# PR9024.net
KiCad netlist of a schematic drawn in EAGLE
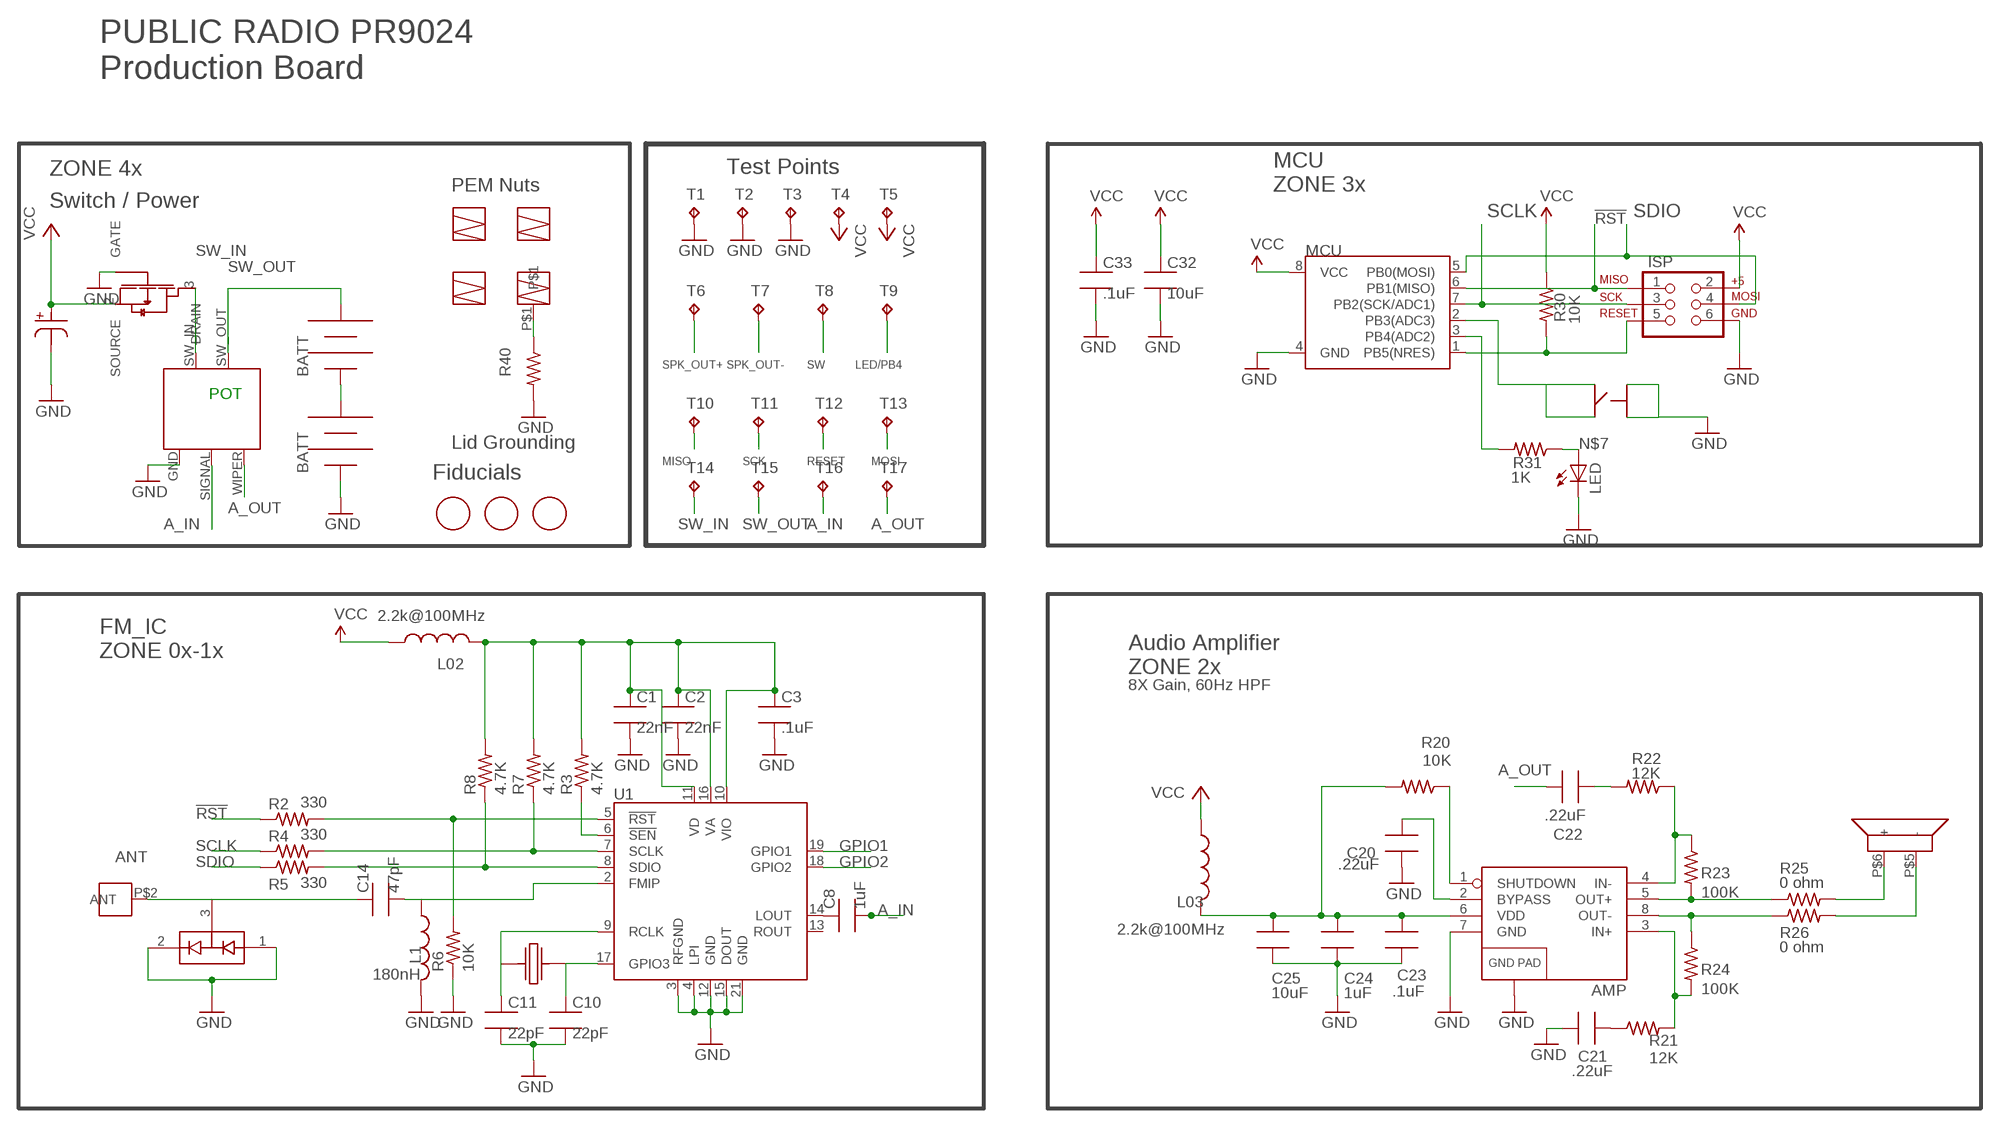
[diagram p0: schematic, sheet 1]

(export (version "E")
  (design (tool "Eeschema 10.0.6"))
  (components
    (comp (ref "AMP")
      (value "TPA6203A1")
      (footprint "eagle-import:8-MSOP")
      (libsource (lib "eagle-import") (part "TPA6203A1"))
    )
    (comp (ref "ANT_MOUNT")
      (value "DNP")
      (footprint "eagle-import:PEM_M3")
      (libsource (lib "eagle-import") (part "M3_PEMNUT"))
    )
    (comp (ref "C1")
      (value "22nF")
      (footprint "eagle-import:0603_CPL")
      (fields
        (field (name "MFG_PN") "CL10B223KB8NNNC")
        (field (name "TOL") "10%")
        (field (name "VOLTAGE") "16V")
      )
      (libsource (lib "eagle-import") (part "C_SMT_0603_CPL"))
    )
    (comp (ref "C2")
      (value "22nF")
      (footprint "eagle-import:0603_CPL")
      (fields
        (field (name "MFG_PN") "CL10B223KB8NNNC")
        (field (name "TOL") "10%")
        (field (name "VOLTAGE") "16V")
      )
      (libsource (lib "eagle-import") (part "C_SMT_0603_CPL"))
    )
    (comp (ref "C3")
      (value ".1uF")
      (footprint "eagle-import:0603_CPL")
      (fields
        (field (name "MFG_PN") "CL10B104KB8SFNC")
        (field (name "TOL") "10%")
        (field (name "VOLTAGE") "16V")
      )
      (libsource (lib "eagle-import") (part "C_SMT_0603_CPL"))
    )
    (comp (ref "C8")
      (value "1uF")
      (footprint "eagle-import:0603_CPL")
      (fields
        (field (name "MFG_PN") "CL10B105KP8NNNC")
        (field (name "TOL") "10%")
        (field (name "VOLTAGE") "10V")
      )
      (libsource (lib "eagle-import") (part "C_SMT_0603_CPL"))
    )
    (comp (ref "C10")
      (value "22pF")
      (footprint "eagle-import:0603_CPL")
      (fields
        (field (name "MFG_PN") "C1608C0G1H220J080AA")
        (field (name "TOL") "5%")
        (field (name "VOLTAGE") "50V")
      )
      (libsource (lib "eagle-import") (part "C_SMT_0603_CPL"))
    )
    (comp (ref "C11")
      (value "22pF")
      (footprint "eagle-import:0603_CPL")
      (fields
        (field (name "MFG_PN") "C1608C0G1H220J080AA")
        (field (name "TOL") "5%")
        (field (name "VOLTAGE") "50V")
      )
      (libsource (lib "eagle-import") (part "C_SMT_0603_CPL"))
    )
    (comp (ref "C14")
      (value "47pF")
      (footprint "eagle-import:0603_CPL")
      (fields
        (field (name "MFG_PN") "CL10C470JB8NCNC")
        (field (name "TOL") "5%")
        (field (name "VOLTAGE") "50V")
      )
      (libsource (lib "eagle-import") (part "C_SMT_0603_CPL"))
    )
    (comp (ref "C20")
      (value ".22uF")
      (footprint "eagle-import:0603_CPL")
      (fields
        (field (name "MFG_PN") "C1608X7R1C224K080AC")
        (field (name "TOL") "10%")
        (field (name "VOLTAGE") "16V")
      )
      (libsource (lib "eagle-import") (part "C_SMT_0603_CPL"))
    )
    (comp (ref "C21")
      (value ".22uF")
      (footprint "eagle-import:0603_CPL")
      (fields
        (field (name "MFG_PN") "C1608X7R1C224K080AC")
        (field (name "TOL") "10%")
        (field (name "VOLTAGE") "16V")
      )
      (libsource (lib "eagle-import") (part "C_SMT_0603_CPL"))
    )
    (comp (ref "C22")
      (value ".22uF")
      (footprint "eagle-import:0603_CPL")
      (fields
        (field (name "MFG_PN") "C1608X7R1C224K080AC")
        (field (name "TOL") "10%")
        (field (name "VOLTAGE") "16V")
      )
      (libsource (lib "eagle-import") (part "C_SMT_0603_CPL"))
    )
    (comp (ref "C23")
      (value ".1uF")
      (footprint "eagle-import:0603_CPL")
      (fields
        (field (name "MFG_PN") "CL10B104KB8SFNC")
        (field (name "TOL") "10%")
        (field (name "VOLTAGE") "16V")
      )
      (libsource (lib "eagle-import") (part "C_SMT_0603_CPL"))
    )
    (comp (ref "C24")
      (value "1uF")
      (footprint "eagle-import:0603_CPL")
      (fields
        (field (name "MFG_PN") "CL10B105KP8NNNC")
        (field (name "TOL") "10%")
        (field (name "VOLTAGE") "10V")
      )
      (libsource (lib "eagle-import") (part "C_SMT_0603_CPL"))
    )
    (comp (ref "C25")
      (value "10uF")
      (footprint "eagle-import:0603_CPL")
      (fields
        (field (name "MFG_PN") "CL10A106MQ8NNNC")
        (field (name "TOL") "20%")
        (field (name "VOLTAGE") "6.3V")
      )
      (libsource (lib "eagle-import") (part "C_SMT_0603_CPL"))
    )
    (comp (ref "C32")
      (value "10uF")
      (footprint "eagle-import:0603_CPL")
      (fields
        (field (name "MFG_PN") "CL10A106MQ8NNNC")
        (field (name "TOL") "20%")
        (field (name "VOLTAGE") "6.3V")
      )
      (libsource (lib "eagle-import") (part "C_SMT_0603_CPL"))
    )
    (comp (ref "C33")
      (value ".1uF")
      (footprint "eagle-import:0603_CPL")
      (fields
        (field (name "MFG_PN") "CL10B104KB8SFNC")
        (field (name "TOL") "10%")
        (field (name "VOLTAGE") "16V")
      )
      (libsource (lib "eagle-import") (part "C_SMT_0603_CPL"))
    )
    (comp (ref "C40")
      (value "220uF")
      (footprint "eagle-import:NICHICON_UD_63")
      (fields (field (name "TOL") "20%") (field (name "VOLTAGE") "16V"))
      (libsource (lib "eagle-import") (part "NICHICON_SERIESUD"))
    )
    (comp (ref "D1")
      (value "BAV99")
      (footprint "eagle-import:SOT23_CPL")
      (fields (field (name "MFG_PN") "BAV99,215"))
      (libsource (lib "eagle-import") (part "BAV99"))
    )
    (comp (ref "FET1")
      (value "AO3435")
      (footprint "eagle-import:SOT23_CPL")
      (fields (field (name "MFG_PN") "AO3435"))
      (libsource (lib "eagle-import") (part "AO3435"))
    )
    (comp (ref "ISP")
      (value "AVR_SPI_PRG_6NS")
      (footprint "eagle-import:2X3-NS")
      (libsource (lib "eagle-import") (part "AVR_SPI_PRG_6NS"))
    )
    (comp (ref "JP5")
      (value "BK-92_MPD_AA_BATT_CLIP")
      (footprint "eagle-import:BK92_AA_BATT")
      (fields (field (name "MFG_PN") "2 of BK92 - supplied by CL Labs"))
      (libsource (lib "eagle-import") (part "BK-92_MPD_AA_BATT_CLIP"))
    )
    (comp (ref "JP6")
      (value "BK-92_MPD_AA_BATT_CLIP")
      (footprint "eagle-import:BK92_AA_BATT")
      (fields (field (name "MFG_PN") "2 of BK92 - supplied by CL Labs"))
      (libsource (lib "eagle-import") (part "BK-92_MPD_AA_BATT_CLIP"))
    )
    (comp (ref "L1")
      (value "180nH")
      (footprint "eagle-import:0805_ADAFRUIT")
      (fields
        (field (name "CURRENT") "400mA")
        (field (name "DCR") "640m")
        (field (name "MFG_PN") "AISC-0805-R18J-T")
        (field (name "TOL") "5%")
      )
      (libsource (lib "eagle-import") (part "L_SMT_0805_ADAFRUIT"))
    )
    (comp (ref "L02")
      (value "2.2k@100MHz")
      (footprint "eagle-import:0603_CPL")
      (fields
        (field (name "CURRENT") "150mA")
        (field (name "DCR") "2.3")
        (field (name "MFG_PN") "HZ0603A222R-10")
      )
      (libsource (lib "eagle-import") (part "L_SMT_0603_CPL"))
    )
    (comp (ref "L03")
      (value "2.2k@100MHz")
      (footprint "eagle-import:0603_CPL")
      (fields
        (field (name "CURRENT") "150mA")
        (field (name "DCR") "2.3")
        (field (name "MFG_PN") "HZ0603A222R-10")
      )
      (libsource (lib "eagle-import") (part "L_SMT_0603_CPL"))
    )
    (comp (ref "LED")
      (value "HSMC-C265_REVERSE_MOUNT_LED")
      (footprint "eagle-import:HSMC-C265_REVERSE_MOUN_LED")
      (libsource (lib "eagle-import") (part "HSMC-C265_REVERSE_MOUNT_LED"))
    )
    (comp (ref "MARK1")
      (value "FIDUCIAL")
      (footprint "eagle-import:FIDUCIAL_1MM")
      (libsource (lib "eagle-import") (part "FIDUCIAL"))
    )
    (comp (ref "MARK2")
      (value "FIDUCIAL")
      (footprint "eagle-import:FIDUCIAL_1MM")
      (libsource (lib "eagle-import") (part "FIDUCIAL"))
    )
    (comp (ref "MARK3")
      (value "FIDUCIAL")
      (footprint "eagle-import:FIDUCIAL_1MM")
      (libsource (lib "eagle-import") (part "FIDUCIAL"))
    )
    (comp (ref "MCU")
      (value "ATTINY45TINY45-20-SMT")
      (footprint "eagle-import:8-SOIC")
      (libsource (lib "eagle-import") (part "ATTINY45TINY45-20-SMT"))
    )
    (comp (ref "R1")
      (value "VOLUME_POT")
      (footprint "eagle-import:H17112NS_A10K_L20F-002")
      (libsource (lib "eagle-import") (part "VOLUME_POT"))
    )
    (comp (ref "R2")
      (value "330")
      (footprint "eagle-import:0603_CPL")
      (fields (field (name "MFG_PN") "MCR03ERTJ331") (field (name "POWER") "1/10W") (field (name "TOL") "5%"))
      (libsource (lib "eagle-import") (part "R_SMT_R0603_CPL"))
    )
    (comp (ref "R3")
      (value "4.7K")
      (footprint "eagle-import:0603_CPL")
      (fields
        (field (name "MFG_PN") "ERJ-3EKF4701V")
        (field (name "POWER") "1/10W")
        (field (name "TOL") "1%")
      )
      (libsource (lib "eagle-import") (part "R_SMT_R0603_CPL"))
    )
    (comp (ref "R4")
      (value "330")
      (footprint "eagle-import:0603_CPL")
      (fields (field (name "MFG_PN") "MCR03ERTJ331") (field (name "POWER") "1/10W") (field (name "TOL") "5%"))
      (libsource (lib "eagle-import") (part "R_SMT_R0603_CPL"))
    )
    (comp (ref "R5")
      (value "330")
      (footprint "eagle-import:0603_CPL")
      (fields (field (name "MFG_PN") "MCR03ERTJ331") (field (name "POWER") "1/10W") (field (name "TOL") "5%"))
      (libsource (lib "eagle-import") (part "R_SMT_R0603_CPL"))
    )
    (comp (ref "R6")
      (value "10K")
      (footprint "eagle-import:0603_CPL")
      (fields
        (field (name "MFG_PN") "ERJ-3GEYJ103V")
        (field (name "POWER") "1/10W")
        (field (name "TOL") "5%")
      )
      (libsource (lib "eagle-import") (part "R_SMT_R0603_CPL"))
    )
    (comp (ref "R7")
      (value "4.7K")
      (footprint "eagle-import:0603_CPL")
      (fields
        (field (name "MFG_PN") "ERJ-3EKF4701V")
        (field (name "POWER") "1/10W")
        (field (name "TOL") "1%")
      )
      (libsource (lib "eagle-import") (part "R_SMT_R0603_CPL"))
    )
    (comp (ref "R8")
      (value "4.7K")
      (footprint "eagle-import:0603_CPL")
      (fields
        (field (name "MFG_PN") "ERJ-3EKF4701V")
        (field (name "POWER") "1/10W")
        (field (name "TOL") "1%")
      )
      (libsource (lib "eagle-import") (part "R_SMT_R0603_CPL"))
    )
    (comp (ref "R20")
      (value "10K")
      (footprint "eagle-import:0603_CPL")
      (fields
        (field (name "MFG_PN") "ERJ-3GEYJ103V")
        (field (name "POWER") "1/10W")
        (field (name "TOL") "5%")
      )
      (libsource (lib "eagle-import") (part "R_SMT_R0603_CPL"))
    )
    (comp (ref "R21")
      (value "12K")
      (footprint "eagle-import:0603_CPL")
      (fields
        (field (name "MFG_PN") "RC0603FR-0712KL")
        (field (name "POWER") "1/10W")
        (field (name "TOL") "1%")
      )
      (libsource (lib "eagle-import") (part "R_SMT_R0603_CPL"))
    )
    (comp (ref "R22")
      (value "12K")
      (footprint "eagle-import:0603_CPL")
      (fields
        (field (name "MFG_PN") "RC0603FR-0712KL")
        (field (name "POWER") "1/10W")
        (field (name "TOL") "1%")
      )
      (libsource (lib "eagle-import") (part "R_SMT_R0603_CPL"))
    )
    (comp (ref "R23")
      (value "100K")
      (footprint "eagle-import:0603_CPL")
      (fields
        (field (name "MFG_PN") "ERJ-3EKF1003V")
        (field (name "POWER") "1/10W")
        (field (name "TOL") "1%")
      )
      (libsource (lib "eagle-import") (part "R_SMT_R0603_CPL"))
    )
    (comp (ref "R24")
      (value "100K")
      (footprint "eagle-import:0603_CPL")
      (fields
        (field (name "MFG_PN") "ERJ-3EKF1003V")
        (field (name "POWER") "1/10W")
        (field (name "TOL") "1%")
      )
      (libsource (lib "eagle-import") (part "R_SMT_R0603_CPL"))
    )
    (comp (ref "R25")
      (value "0 ohm")
      (footprint "eagle-import:0805_ADAFRUIT")
      (fields (field (name "MFG_PN") "ERJ-6GEY0R00V "))
      (libsource (lib "eagle-import") (part "R_SMT_0805_ADAFRUIT"))
    )
    (comp (ref "R26")
      (value "0 ohm")
      (footprint "eagle-import:0805_ADAFRUIT")
      (fields (field (name "MFG_PN") "ERJ-6GEY0R00V "))
      (libsource (lib "eagle-import") (part "R_SMT_0805_ADAFRUIT"))
    )
    (comp (ref "R30")
      (value "10K")
      (footprint "eagle-import:0603_CPL")
      (fields
        (field (name "MFG_PN") "ERJ-3GEYJ103V")
        (field (name "POWER") "1/10W")
        (field (name "TOL") "5%")
      )
      (libsource (lib "eagle-import") (part "R_SMT_R0603_CPL"))
    )
    (comp (ref "R31")
      (value "1K")
      (footprint "eagle-import:0603_CPL")
      (fields
        (field (name "MFG_PN") "ERJ-3EKF1001V")
        (field (name "POWER") "1/10W")
        (field (name "TOL") "1%")
      )
      (libsource (lib "eagle-import") (part "R_SMT_R0603_CPL"))
    )
    (comp (ref "R40")
      (value "DNP")
      (footprint "eagle-import:0603_CPL")
      (fields (field (name "MFG_PN") "ERJ-3GEY0R00V"))
      (libsource (lib "eagle-import") (part "R_SMT_R0603_CPL"))
    )
    (comp (ref "SPKR_PLACE")
      (value "DNP")
      (footprint "eagle-import:PR2024_SPKR_PLACE(SMD)")
      (libsource (lib "eagle-import") (part "PR2024_SPKR_SMD"))
    )
    (comp (ref "SW1")
      (value "C&K_PTS645")
      (footprint "eagle-import:C&K_PTS645_SMT")
      (libsource (lib "eagle-import") (part "C&K_PTS645"))
    )
    (comp (ref "T1")
      (value "TPTP20R")
      (footprint "eagle-import:TP20R")
      (libsource (lib "eagle-import") (part "TPTP20R"))
    )
    (comp (ref "T2")
      (value "TPTP20R")
      (footprint "eagle-import:TP20R")
      (libsource (lib "eagle-import") (part "TPTP20R"))
    )
    (comp (ref "T3")
      (value "TPTP20R")
      (footprint "eagle-import:TP20R")
      (libsource (lib "eagle-import") (part "TPTP20R"))
    )
    (comp (ref "T4")
      (value "TPTP20R")
      (footprint "eagle-import:TP20R")
      (libsource (lib "eagle-import") (part "TPTP20R"))
    )
    (comp (ref "T5")
      (value "TPTP20R")
      (footprint "eagle-import:TP20R")
      (libsource (lib "eagle-import") (part "TPTP20R"))
    )
    (comp (ref "T6")
      (value "TPTP20R")
      (footprint "eagle-import:TP20R")
      (libsource (lib "eagle-import") (part "TPTP20R"))
    )
    (comp (ref "T7")
      (value "TPTP20R")
      (footprint "eagle-import:TP20R")
      (libsource (lib "eagle-import") (part "TPTP20R"))
    )
    (comp (ref "T8")
      (value "TPTP20R")
      (footprint "eagle-import:TP20R")
      (libsource (lib "eagle-import") (part "TPTP20R"))
    )
    (comp (ref "T9")
      (value "TPTP20R")
      (footprint "eagle-import:TP20R")
      (libsource (lib "eagle-import") (part "TPTP20R"))
    )
    (comp (ref "T10")
      (value "TPTP20R")
      (footprint "eagle-import:TP20R")
      (libsource (lib "eagle-import") (part "TPTP20R"))
    )
    (comp (ref "T11")
      (value "TPTP20R")
      (footprint "eagle-import:TP20R")
      (libsource (lib "eagle-import") (part "TPTP20R"))
    )
    (comp (ref "T12")
      (value "TPTP20R")
      (footprint "eagle-import:TP20R")
      (libsource (lib "eagle-import") (part "TPTP20R"))
    )
    (comp (ref "T13")
      (value "TPTP20R")
      (footprint "eagle-import:TP20R")
      (libsource (lib "eagle-import") (part "TPTP20R"))
    )
    (comp (ref "T14")
      (value "TPTP20R")
      (footprint "eagle-import:TP20R")
      (libsource (lib "eagle-import") (part "TPTP20R"))
    )
    (comp (ref "T15")
      (value "TPTP20R")
      (footprint "eagle-import:TP20R")
      (libsource (lib "eagle-import") (part "TPTP20R"))
    )
    (comp (ref "T16")
      (value "TPTP20R")
      (footprint "eagle-import:TP20R")
      (libsource (lib "eagle-import") (part "TPTP20R"))
    )
    (comp (ref "T17")
      (value "TPTP20R")
      (footprint "eagle-import:TP20R")
      (libsource (lib "eagle-import") (part "TPTP20R"))
    )
    (comp (ref "U$2")
      (value "PEM_SMT")
      (footprint "eagle-import:PEM_SMT")
      (libsource (lib "eagle-import") (part "PEM_SMT"))
    )
    (comp (ref "U$3")
      (value "PEM_SMT")
      (footprint "eagle-import:PEM_SMT")
      (libsource (lib "eagle-import") (part "PEM_SMT"))
    )
    (comp (ref "U$4")
      (value "PEM_SMT")
      (footprint "eagle-import:PEM_SMT")
      (libsource (lib "eagle-import") (part "PEM_SMT"))
    )
    (comp (ref "U$5")
      (value "PEM_M3_SMT_W/PIN")
      (footprint "eagle-import:PEM_SMT")
      (libsource (lib "eagle-import") (part "PEM_M3_SMT_W/PIN"))
    )
    (comp (ref "U1")
      (value "SI4702-C19-GMR")
      (footprint "eagle-import:SI470X_20_QFN")
      (fields (field (name "MFG_PN") "Si4702 C19 GM - supplied by CL Labs"))
      (libsource (lib "eagle-import") (part "SI4702-C19-GMR"))
    )
    (comp (ref "X1")
      (value "ABS25XTAL")
      (footprint "eagle-import:4-SOJ")
      (libsource (lib "eagle-import") (part "ABS25XTAL"))
    )
  )
  (nets
    (net (code "1") (name "/ANT") (class "Default")
      (node (ref "ANT_MOUNT") (pin "P$2") (pinfunction "ANT_P$2") (pintype "bidirectional"))
      (node (ref "C14") (pin "1") (pinfunction "1_1") (pintype "passive"))
      (node (ref "D1") (pin "3") (pinfunction "COM_3") (pintype "bidirectional"))
    )
    (net (code "2") (name "/A_IN") (class "Default")
      (node (ref "C8") (pin "2") (pinfunction "2_2") (pintype "passive"))
      (node (ref "R1") (pin "SIGNAL") (pinfunction "SIGNAL_SIGNAL") (pintype "bidirectional"))
      (node (ref "T16") (pin "TP") (pinfunction "TP_TP") (pintype "input"))
    )
    (net (code "3") (name "/A_OUT") (class "Default")
      (node (ref "C22") (pin "2") (pinfunction "2_2") (pintype "passive"))
      (node (ref "R1") (pin "WIPER") (pinfunction "WIPER_WIPER") (pintype "bidirectional"))
      (node (ref "T17") (pin "TP") (pinfunction "TP_TP") (pintype "input"))
    )
    (net (code "4") (name "/GPIO1") (class "Default")
      (node (ref "U1") (pin "19") (pinfunction "GPIO1_19") (pintype "bidirectional"))
    )
    (net (code "5") (name "/GPIO2") (class "Default")
      (node (ref "U1") (pin "18") (pinfunction "GPIO2_18") (pintype "bidirectional"))
    )
    (net (code "6") (name "/LED{slash}PB4") (class "Default")
      (node (ref "MCU") (pin "3") (pinfunction "PB4(ADC2)_3") (pintype "bidirectional"))
      (node (ref "R31") (pin "2") (pinfunction "2_2") (pintype "passive"))
      (node (ref "T9") (pin "TP") (pinfunction "TP_TP") (pintype "input"))
    )
    (net (code "7") (name "/N$7") (class "Default")
      (node (ref "LED") (pin "P$1") (pinfunction "A_P$1") (pintype "passive"))
      (node (ref "R31") (pin "1") (pinfunction "1_1") (pintype "passive"))
    )
    (net (code "8") (name "/RESET") (class "Default")
      (node (ref "ISP") (pin "5") (pinfunction "5_5") (pintype "passive"))
      (node (ref "MCU") (pin "1") (pinfunction "PB5(NRES)_1") (pintype "bidirectional"))
      (node (ref "R30") (pin "2") (pinfunction "2_2") (pintype "passive"))
      (node (ref "T12") (pin "TP") (pinfunction "TP_TP") (pintype "input"))
    )
    (net (code "9") (name "/SCLK") (class "Default")
      (node (ref "ISP") (pin "3") (pinfunction "3_3") (pintype "passive"))
      (node (ref "MCU") (pin "7") (pinfunction "PB2(SCK/ADC1)_7") (pintype "bidirectional"))
      (node (ref "R4") (pin "1") (pinfunction "1_1") (pintype "passive"))
      (node (ref "T11") (pin "TP") (pinfunction "TP_TP") (pintype "input"))
    )
    (net (code "10") (name "/SDIO") (class "Default")
      (node (ref "ISP") (pin "4") (pinfunction "4_4") (pintype "passive"))
      (node (ref "MCU") (pin "5") (pinfunction "PB0(MOSI)_5") (pintype "bidirectional"))
      (node (ref "R5") (pin "1") (pinfunction "1_1") (pintype "passive"))
      (node (ref "T13") (pin "TP") (pinfunction "TP_TP") (pintype "input"))
    )
    (net (code "11") (name "/SPK_OUT+") (class "Default")
      (node (ref "R25") (pin "2") (pinfunction "2_2") (pintype "passive"))
      (node (ref "SPKR_PLACE") (pin "P$6") (pinfunction "+_P$6") (pintype "bidirectional"))
      (node (ref "T6") (pin "TP") (pinfunction "TP_TP") (pintype "input"))
    )
    (net (code "12") (name "/SPK_OUT-") (class "Default")
      (node (ref "R26") (pin "2") (pinfunction "2_2") (pintype "passive"))
      (node (ref "SPKR_PLACE") (pin "P$5") (pinfunction "-_P$5") (pintype "bidirectional"))
      (node (ref "T7") (pin "TP") (pinfunction "TP_TP") (pintype "input"))
    )
    (net (code "13") (name "/SW") (class "Default")
      (node (ref "MCU") (pin "2") (pinfunction "PB3(ADC3)_2") (pintype "bidirectional"))
      (node (ref "SW1") (pin "P$3") (pinfunction "P$3_P$3") (pintype "bidirectional"))
      (node (ref "SW1") (pin "P$4") (pinfunction "P$4_P$4") (pintype "bidirectional"))
      (node (ref "T8") (pin "TP") (pinfunction "TP_TP") (pintype "input"))
    )
    (net (code "14") (name "/SW_IN") (class "Default")
      (node (ref "FET1") (pin "3") (pinfunction "DRAIN_3") (pintype "bidirectional"))
      (node (ref "R1") (pin "SW_IN") (pinfunction "SW_IN_SW_IN") (pintype "bidirectional"))
      (node (ref "T14") (pin "TP") (pinfunction "TP_TP") (pintype "input"))
    )
    (net (code "15") (name "/SW_OUT") (class "Default")
      (node (ref "JP5") (pin "POS") (pinfunction "POS_POS") (pintype "bidirectional"))
      (node (ref "JP5") (pin "POS@2") (pinfunction "POS_POS@2") (pintype "bidirectional"))
      (node (ref "R1") (pin "SW_OUT") (pinfunction "SW_OUT_SW_OUT") (pintype "bidirectional"))
      (node (ref "T15") (pin "TP") (pinfunction "TP_TP") (pintype "input"))
    )
    (net (code "16") (name "/~{RST}") (class "Default")
      (node (ref "ISP") (pin "1") (pinfunction "1_1") (pintype "passive"))
      (node (ref "MCU") (pin "6") (pinfunction "PB1(MISO)_6") (pintype "bidirectional"))
      (node (ref "R2") (pin "1") (pinfunction "1_1") (pintype "passive"))
      (node (ref "T10") (pin "TP") (pinfunction "TP_TP") (pintype "input"))
    )
    (net (code "17") (name "GND") (class "Default")
      (node (ref "AMP") (pin "7") (pinfunction "GND_7") (pintype "power_in"))
      (node (ref "AMP") (pin "9") (pinfunction "GND_9") (pintype "power_in"))
      (node (ref "C1") (pin "2") (pinfunction "2_2") (pintype "passive"))
      (node (ref "C10") (pin "2") (pinfunction "2_2") (pintype "passive"))
      (node (ref "C11") (pin "2") (pinfunction "2_2") (pintype "passive"))
      (node (ref "C2") (pin "2") (pinfunction "2_2") (pintype "passive"))
      (node (ref "C20") (pin "1") (pinfunction "1_1") (pintype "passive"))
      (node (ref "C21") (pin "1") (pinfunction "1_1") (pintype "passive"))
      (node (ref "C23") (pin "2") (pinfunction "2_2") (pintype "passive"))
      (node (ref "C24") (pin "2") (pinfunction "2_2") (pintype "passive"))
      (node (ref "C25") (pin "2") (pinfunction "2_2") (pintype "passive"))
      (node (ref "C3") (pin "2") (pinfunction "2_2") (pintype "passive"))
      (node (ref "C32") (pin "2") (pinfunction "2_2") (pintype "passive"))
      (node (ref "C33") (pin "2") (pinfunction "2_2") (pintype "passive"))
      (node (ref "C40") (pin "P$2") (pinfunction "P$2_P$2") (pintype "bidirectional"))
      (node (ref "D1") (pin "1") (pinfunction "A1_1") (pintype "bidirectional"))
      (node (ref "D1") (pin "2") (pinfunction "C2_2") (pintype "bidirectional"))
      (node (ref "FET1") (pin "1") (pinfunction "GATE_1") (pintype "bidirectional"))
      (node (ref "ISP") (pin "6") (pinfunction "6_6") (pintype "passive"))
      (node (ref "JP6") (pin "NEG") (pinfunction "NEG_NEG") (pintype "bidirectional"))
      (node (ref "JP6") (pin "NEG@2") (pinfunction "NEG_NEG@2") (pintype "bidirectional"))
      (node (ref "L1") (pin "2") (pinfunction "2_2") (pintype "passive"))
      (node (ref "LED") (pin "P$2") (pinfunction "C_P$2") (pintype "passive"))
      (node (ref "MCU") (pin "4") (pinfunction "GND_4") (pintype "bidirectional"))
      (node (ref "R1") (pin "GND") (pinfunction "GND_GND") (pintype "bidirectional"))
      (node (ref "R40") (pin "2") (pinfunction "2_2") (pintype "passive"))
      (node (ref "R6") (pin "1") (pinfunction "1_1") (pintype "passive"))
      (node (ref "SW1") (pin "P$1") (pinfunction "P$1_P$1") (pintype "bidirectional"))
      (node (ref "SW1") (pin "P$2") (pinfunction "P$2_P$2") (pintype "bidirectional"))
      (node (ref "T1") (pin "TP") (pinfunction "TP_TP") (pintype "input"))
      (node (ref "T2") (pin "TP") (pinfunction "TP_TP") (pintype "input"))
      (node (ref "T3") (pin "TP") (pinfunction "TP_TP") (pintype "input"))
      (node (ref "U1") (pin "12") (pinfunction "GND_12") (pintype "bidirectional"))
      (node (ref "U1") (pin "15") (pinfunction "DOUT_15") (pintype "bidirectional"))
      (node (ref "U1") (pin "21") (pinfunction "GND_21") (pintype "bidirectional"))
      (node (ref "U1") (pin "3") (pinfunction "RFGND_3") (pintype "bidirectional"))
      (node (ref "U1") (pin "4") (pinfunction "LPI_4") (pintype "bidirectional"))
    )
    (net (code "18") (name "Net-(AMP-BYPASS)") (class "Default")
      (node (ref "AMP") (pin "2") (pinfunction "BYPASS_2") (pintype "bidirectional"))
      (node (ref "C20") (pin "2") (pinfunction "2_2") (pintype "passive"))
    )
    (net (code "19") (name "Net-(AMP-IN+)") (class "Default")
      (node (ref "AMP") (pin "3") (pinfunction "IN+_3") (pintype "bidirectional"))
      (node (ref "R21") (pin "2") (pinfunction "2_2") (pintype "passive"))
      (node (ref "R24") (pin "2") (pinfunction "2_2") (pintype "passive"))
    )
    (net (code "20") (name "Net-(AMP-IN-)") (class "Default")
      (node (ref "AMP") (pin "4") (pinfunction "IN-_4") (pintype "bidirectional"))
      (node (ref "R22") (pin "1") (pinfunction "1_1") (pintype "passive"))
      (node (ref "R23") (pin "1") (pinfunction "1_1") (pintype "passive"))
    )
    (net (code "21") (name "Net-(AMP-OUT+)") (class "Default")
      (node (ref "AMP") (pin "5") (pinfunction "OUT+_5") (pintype "bidirectional"))
      (node (ref "R23") (pin "2") (pinfunction "2_2") (pintype "passive"))
      (node (ref "R25") (pin "1") (pinfunction "1_1") (pintype "passive"))
    )
    (net (code "22") (name "Net-(AMP-OUT-)") (class "Default")
      (node (ref "AMP") (pin "8") (pinfunction "OUT-_8") (pintype "bidirectional"))
      (node (ref "R24") (pin "1") (pinfunction "1_1") (pintype "passive"))
      (node (ref "R26") (pin "1") (pinfunction "1_1") (pintype "passive"))
    )
    (net (code "23") (name "Net-(AMP-SHUTDOWN)") (class "Default")
      (node (ref "AMP") (pin "1") (pinfunction "SHUTDOWN_1") (pintype "input"))
      (node (ref "R20") (pin "1") (pinfunction "1_1") (pintype "passive"))
    )
    (net (code "24") (name "Net-(AMP-VDD)") (class "Default")
      (node (ref "AMP") (pin "6") (pinfunction "VDD_6") (pintype "power_in"))
      (node (ref "C23") (pin "1") (pinfunction "1_1") (pintype "passive"))
      (node (ref "C24") (pin "1") (pinfunction "1_1") (pintype "passive"))
      (node (ref "C25") (pin "1") (pinfunction "1_1") (pintype "passive"))
      (node (ref "L03") (pin "2") (pinfunction "2_2") (pintype "passive"))
      (node (ref "R20") (pin "2") (pinfunction "2_2") (pintype "passive"))
    )
    (net (code "25") (name "Net-(C21-Pad2)") (class "Default")
      (node (ref "C21") (pin "2") (pinfunction "2_2") (pintype "passive"))
      (node (ref "R21") (pin "1") (pinfunction "1_1") (pintype "passive"))
    )
    (net (code "26") (name "Net-(C22-Pad1)") (class "Default")
      (node (ref "C22") (pin "1") (pinfunction "1_1") (pintype "passive"))
      (node (ref "R22") (pin "2") (pinfunction "2_2") (pintype "passive"))
    )
    (net (code "27") (name "Net-(JP5-NEG-PadNEG@2)") (class "Default")
      (node (ref "JP5") (pin "NEG") (pinfunction "NEG_NEG") (pintype "bidirectional"))
      (node (ref "JP5") (pin "NEG@2") (pinfunction "NEG_NEG@2") (pintype "bidirectional"))
      (node (ref "JP6") (pin "POS") (pinfunction "POS_POS") (pintype "bidirectional"))
      (node (ref "JP6") (pin "POS@2") (pinfunction "POS_POS@2") (pintype "bidirectional"))
    )
    (net (code "28") (name "Net-(R40-Pad1)") (class "Default")
      (node (ref "R40") (pin "1") (pinfunction "1_1") (pintype "passive"))
      (node (ref "U$5") (pin "P$1") (pinfunction "P$1_P$1") (pintype "bidirectional"))
    )
    (net (code "29") (name "Net-(U1-FMIP)") (class "Default")
      (node (ref "C14") (pin "2") (pinfunction "2_2") (pintype "passive"))
      (node (ref "L1") (pin "1") (pinfunction "1_1") (pintype "passive"))
      (node (ref "U1") (pin "2") (pinfunction "FMIP_2") (pintype "bidirectional"))
    )
    (net (code "30") (name "Net-(U1-GPIO3)") (class "Default")
      (node (ref "C10") (pin "1") (pinfunction "1_1") (pintype "passive"))
      (node (ref "U1") (pin "17") (pinfunction "GPIO3_17") (pintype "bidirectional"))
      (node (ref "X1") (pin "P$4") (pinfunction "P$4_P$4") (pintype "bidirectional"))
    )
    (net (code "31") (name "Net-(U1-LOUT)") (class "Default")
      (node (ref "C8") (pin "1") (pinfunction "1_1") (pintype "passive"))
      (node (ref "U1") (pin "14") (pinfunction "LOUT_14") (pintype "bidirectional"))
    )
    (net (code "32") (name "Net-(U1-RCLK)") (class "Default")
      (node (ref "C11") (pin "1") (pinfunction "1_1") (pintype "passive"))
      (node (ref "U1") (pin "9") (pinfunction "RCLK_9") (pintype "bidirectional"))
      (node (ref "X1") (pin "P$1") (pinfunction "P$1_P$1") (pintype "bidirectional"))
    )
    (net (code "33") (name "Net-(U1-SCLK)") (class "Default")
      (node (ref "R4") (pin "2") (pinfunction "2_2") (pintype "passive"))
      (node (ref "R7") (pin "1") (pinfunction "1_1") (pintype "passive"))
      (node (ref "U1") (pin "7") (pinfunction "SCLK_7") (pintype "bidirectional"))
    )
    (net (code "34") (name "Net-(U1-SDIO)") (class "Default")
      (node (ref "R5") (pin "2") (pinfunction "2_2") (pintype "passive"))
      (node (ref "R8") (pin "1") (pinfunction "1_1") (pintype "passive"))
      (node (ref "U1") (pin "8") (pinfunction "SDIO_8") (pintype "bidirectional"))
    )
    (net (code "35") (name "Net-(U1-VA)") (class "Default")
      (node (ref "C1") (pin "1") (pinfunction "1_1") (pintype "passive"))
      (node (ref "C2") (pin "1") (pinfunction "1_1") (pintype "passive"))
      (node (ref "C3") (pin "1") (pinfunction "1_1") (pintype "passive"))
      (node (ref "L02") (pin "2") (pinfunction "2_2") (pintype "passive"))
      (node (ref "R3") (pin "2") (pinfunction "2_2") (pintype "passive"))
      (node (ref "R7") (pin "2") (pinfunction "2_2") (pintype "passive"))
      (node (ref "R8") (pin "2") (pinfunction "2_2") (pintype "passive"))
      (node (ref "U1") (pin "10") (pinfunction "VIO_10") (pintype "bidirectional"))
      (node (ref "U1") (pin "11") (pinfunction "VD_11") (pintype "bidirectional"))
      (node (ref "U1") (pin "16") (pinfunction "VA_16") (pintype "bidirectional"))
    )
    (net (code "36") (name "Net-(U1-~{RST})") (class "Default")
      (node (ref "R2") (pin "2") (pinfunction "2_2") (pintype "passive"))
      (node (ref "R6") (pin "2") (pinfunction "2_2") (pintype "passive"))
      (node (ref "U1") (pin "5") (pinfunction "~{RST}_5") (pintype "bidirectional"))
    )
    (net (code "37") (name "Net-(U1-~{SEN})") (class "Default")
      (node (ref "R3") (pin "1") (pinfunction "1_1") (pintype "passive"))
      (node (ref "U1") (pin "6") (pinfunction "~{SEN}_6") (pintype "bidirectional"))
    )
    (net (code "38") (name "VCC") (class "Default")
      (node (ref "C32") (pin "1") (pinfunction "1_1") (pintype "passive"))
      (node (ref "C33") (pin "1") (pinfunction "1_1") (pintype "passive"))
      (node (ref "C40") (pin "P$1") (pinfunction "P$1_P$1") (pintype "bidirectional"))
      (node (ref "FET1") (pin "2") (pinfunction "SOURCE_2") (pintype "bidirectional"))
      (node (ref "ISP") (pin "2") (pinfunction "2_2") (pintype "passive"))
      (node (ref "L02") (pin "1") (pinfunction "1_1") (pintype "passive"))
      (node (ref "L03") (pin "1") (pinfunction "1_1") (pintype "passive"))
      (node (ref "MCU") (pin "8") (pinfunction "VCC_8") (pintype "bidirectional"))
      (node (ref "R30") (pin "1") (pinfunction "1_1") (pintype "passive"))
      (node (ref "T4") (pin "TP") (pinfunction "TP_TP") (pintype "input"))
      (node (ref "T5") (pin "TP") (pinfunction "TP_TP") (pintype "input"))
    )
    (net (code "39") (name "unconnected-(U1-ROUT-Pad13)") (class "Default")
      (node (ref "U1") (pin "13") (pinfunction "ROUT_13") (pintype "bidirectional"))
    )
  )
)
